# ImpedanceMatcher.net
KiCad netlist of a schematic drawn in Altium Designer
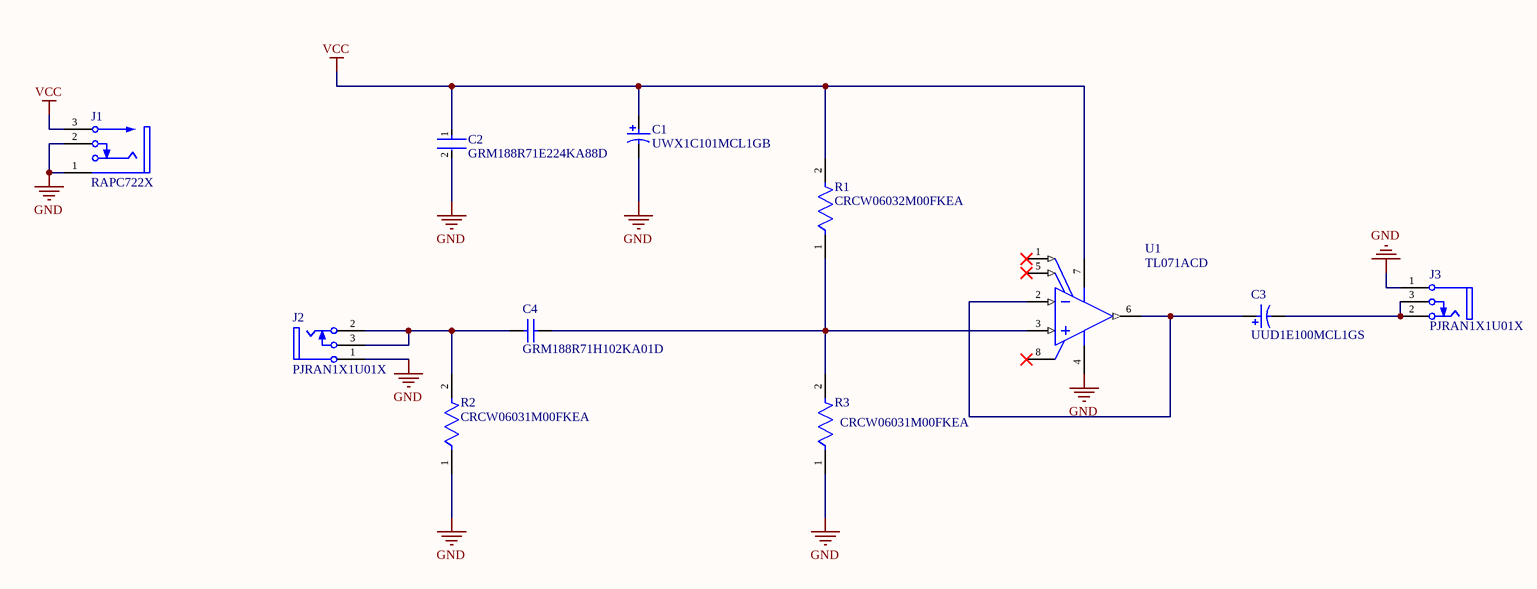
[diagram p0: ImpedanceMatcher.SchDoc]

(export (version "E")
  (design (tool "Eeschema 10.0.6"))
  (components
    (comp (ref "C1")
      (value "UWX1C101MCL1GB")
      (footprint "CAPAE7067X55L")
      (fields (field (name "MANUFACTURER") "Nichicon"))
      (libsource (lib "Altium Content Vault") (part "CAP-P-2"))
    )
    (comp (ref "C2")
      (value "GRM188R71E224KA88D")
      (footprint "FP-GRM188-0_1-e0_2_0_5-IPC_C")
      (description "Chip Multilayer Ceramic Capacitors for General Purpose, 0603, 0.22uF, X7R, 15%, 10%, 25V")
      (fields (field (name "TOLERANCE") "10%") (field (name "VOLTAGE") "50V"))
      (libsource (lib "Altium Content Vault") (part "11868f565c42a9108669ba33697ecf6"))
    )
    (comp (ref "C3")
      (value "UUD1E100MCL1GS")
      (footprint "NIC-CAPA2-4X5.8_V")
      (fields (field (name "MANUFACTURER") "Nichicon"))
      (libsource (lib "Altium Content Vault") (part "NIC-CAP-P-2"))
    )
    (comp (ref "C4")
      (value "GRM188R71H102KA01D")
      (footprint "CAPC1608X90X35NL10T15")
      (fields (field (name "MANUFACTURER") "Murata"))
      (libsource (lib "Altium Content Vault") (part "CAP"))
    )
    (comp (ref "J1")
      (value "RAPC722X")
      (footprint "SWITCH-RAPC712X-3_V")
      (description "Power Jack, 5 A, 3-Pin THD, RoHS, Bulk")
      (fields (field (name "MANUFACTURER") "Switchcraft"))
      (libsource (lib "Altium Content Vault") (part "SWITCH-RAPC712X-3"))
    )
    (comp (ref "J2")
      (value "PJRAN1X1U01X")
      (footprint "SWIT-PJRAN1X1U01X_V")
      (description "Female Phono Jack, 3 Position, Height 13 mm, Tail Length 4 mm, RoHS, Bulk")
      (fields (field (name "TOLERANCE") "10%"))
      (libsource (lib "Altium Content Vault") (part "JACK-2CD3-TN"))
    )
    (comp (ref "J3")
      (value "PJRAN1X1U01X")
      (footprint "SWIT-PJRAN1X1U01X_V")
      (description "Female Phono Jack, 3 Position, Height 13 mm, Tail Length 4 mm, RoHS, Bulk")
      (fields (field (name "TOLERANCE") "10%"))
      (libsource (lib "Altium Content Vault") (part "JACK-2CD3-TN"))
    )
    (comp (ref "R1")
      (value "CRCW06032M00FKEA")
      (footprint "FP-CRCW0603-e3-IPC_A")
      (description "RES Thick Film, 2MΩ, 1%, 0.1W, 100ppm/°C, 0603")
      (fields (field (name "TOLERANCE") "1%"))
      (libsource (lib "Altium Content Vault") (part "1029c3af85768c4190bb7ad29bc67b5"))
    )
    (comp (ref "R2")
      (value "CRCW06031M00FKEA")
      (footprint "FP-CRCW0603-e3-MFG")
      (description "RES Thick Film, 1MΩ, 1%, 0.1W, 100ppm/°C, 0603")
      (fields (field (name "TOLERANCE") "1%"))
      (libsource (lib "Altium Content Vault") (part "1029c3af85768c4190bb7ad29bc67b5"))
    )
    (comp (ref "R3")
      (value "CRCW06031M00FKEA")
      (footprint "FP-CRCW0603-e3-MFG")
      (description "RES Thick Film, 1MΩ, 1%, 0.1W, 100ppm/°C, 0603")
      (fields (field (name "TOLERANCE") "1%"))
      (libsource (lib "Altium Content Vault") (part "1029c3af85768c4190bb7ad29bc67b5"))
    )
    (comp (ref "U1")
      (value "TL071ACD")
      (footprint "D0008A_M")
      (fields (field (name "MANUFACTURER") "Texas Instruments"))
      (libsource (lib "Altium Content Vault") (part "TI-AMP-S5-2-8"))
    )
  )
  (nets
    (net (code "1") (name "GND") (class "Default")
      (node (ref "C1") (pin "2") (pinfunction "2_2") (pintype "passive"))
      (node (ref "C2") (pin "2") (pinfunction "2_2") (pintype "passive"))
      (node (ref "J1") (pin "1") (pinfunction "1_1") (pintype "passive"))
      (node (ref "J1") (pin "2") (pinfunction "2_2") (pintype "passive"))
      (node (ref "J2") (pin "1") (pinfunction "SLEEVE_1") (pintype "passive"))
      (node (ref "J3") (pin "1") (pinfunction "SLEEVE_1") (pintype "passive"))
      (node (ref "R2") (pin "1") (pinfunction "1_1") (pintype "passive"))
      (node (ref "R3") (pin "1") (pinfunction "1_1") (pintype "passive"))
      (node (ref "U1") (pin "4") (pinfunction "VCC-_4") (pintype "power_in"))
    )
    (net (code "2") (name "Net-(J2-SHUNT)") (class "Default")
      (node (ref "C4") (pin "1") (pinfunction "1_1") (pintype "passive"))
      (node (ref "J2") (pin "2") (pinfunction "TIP_2") (pintype "passive"))
      (node (ref "J2") (pin "3") (pinfunction "SHUNT_3") (pintype "passive"))
      (node (ref "R2") (pin "2") (pinfunction "2_2") (pintype "passive"))
    )
    (net (code "3") (name "Net-(J3-SHUNT)") (class "Default")
      (node (ref "C3") (pin "2") (pinfunction "2_2") (pintype "passive"))
      (node (ref "J3") (pin "2") (pinfunction "TIP_2") (pintype "passive"))
      (node (ref "J3") (pin "3") (pinfunction "SHUNT_3") (pintype "passive"))
    )
    (net (code "4") (name "Net-(U1-IN+)") (class "Default")
      (node (ref "C4") (pin "2") (pinfunction "2_2") (pintype "passive"))
      (node (ref "R1") (pin "1") (pinfunction "1_1") (pintype "passive"))
      (node (ref "R3") (pin "2") (pinfunction "2_2") (pintype "passive"))
      (node (ref "U1") (pin "3") (pinfunction "IN+_3") (pintype "input"))
    )
    (net (code "5") (name "Net-(U1-IN-)") (class "Default")
      (node (ref "C3") (pin "1") (pinfunction "1_1") (pintype "passive"))
      (node (ref "U1") (pin "2") (pinfunction "IN-_2") (pintype "input"))
      (node (ref "U1") (pin "6") (pinfunction "OUT_6") (pintype "output"))
    )
    (net (code "6") (name "VCC") (class "Default")
      (node (ref "C1") (pin "1") (pinfunction "1_1") (pintype "passive"))
      (node (ref "C2") (pin "1") (pinfunction "1_1") (pintype "passive"))
      (node (ref "J1") (pin "3") (pinfunction "3_3") (pintype "passive"))
      (node (ref "R1") (pin "2") (pinfunction "2_2") (pintype "passive"))
      (node (ref "U1") (pin "7") (pinfunction "VCC+_7") (pintype "power_in"))
    )
    (net (code "7") (name "unconnected-(U1-NC-Pad8)") (class "Default")
      (node (ref "U1") (pin "8") (pinfunction "NC_8") (pintype "passive+no_connect"))
    )
    (net (code "8") (name "unconnected-(U1-OFFSET_N1-Pad1)") (class "Default")
      (node (ref "U1") (pin "1") (pinfunction "OFFSET_N1_1") (pintype "input+no_connect"))
    )
    (net (code "9") (name "unconnected-(U1-OFFSET_N2-Pad5)") (class "Default")
      (node (ref "U1") (pin "5") (pinfunction "OFFSET_N2_5") (pintype "input+no_connect"))
    )
  )
)
